# devBoard.net
KiCad netlist of a schematic drawn in Altium Designer
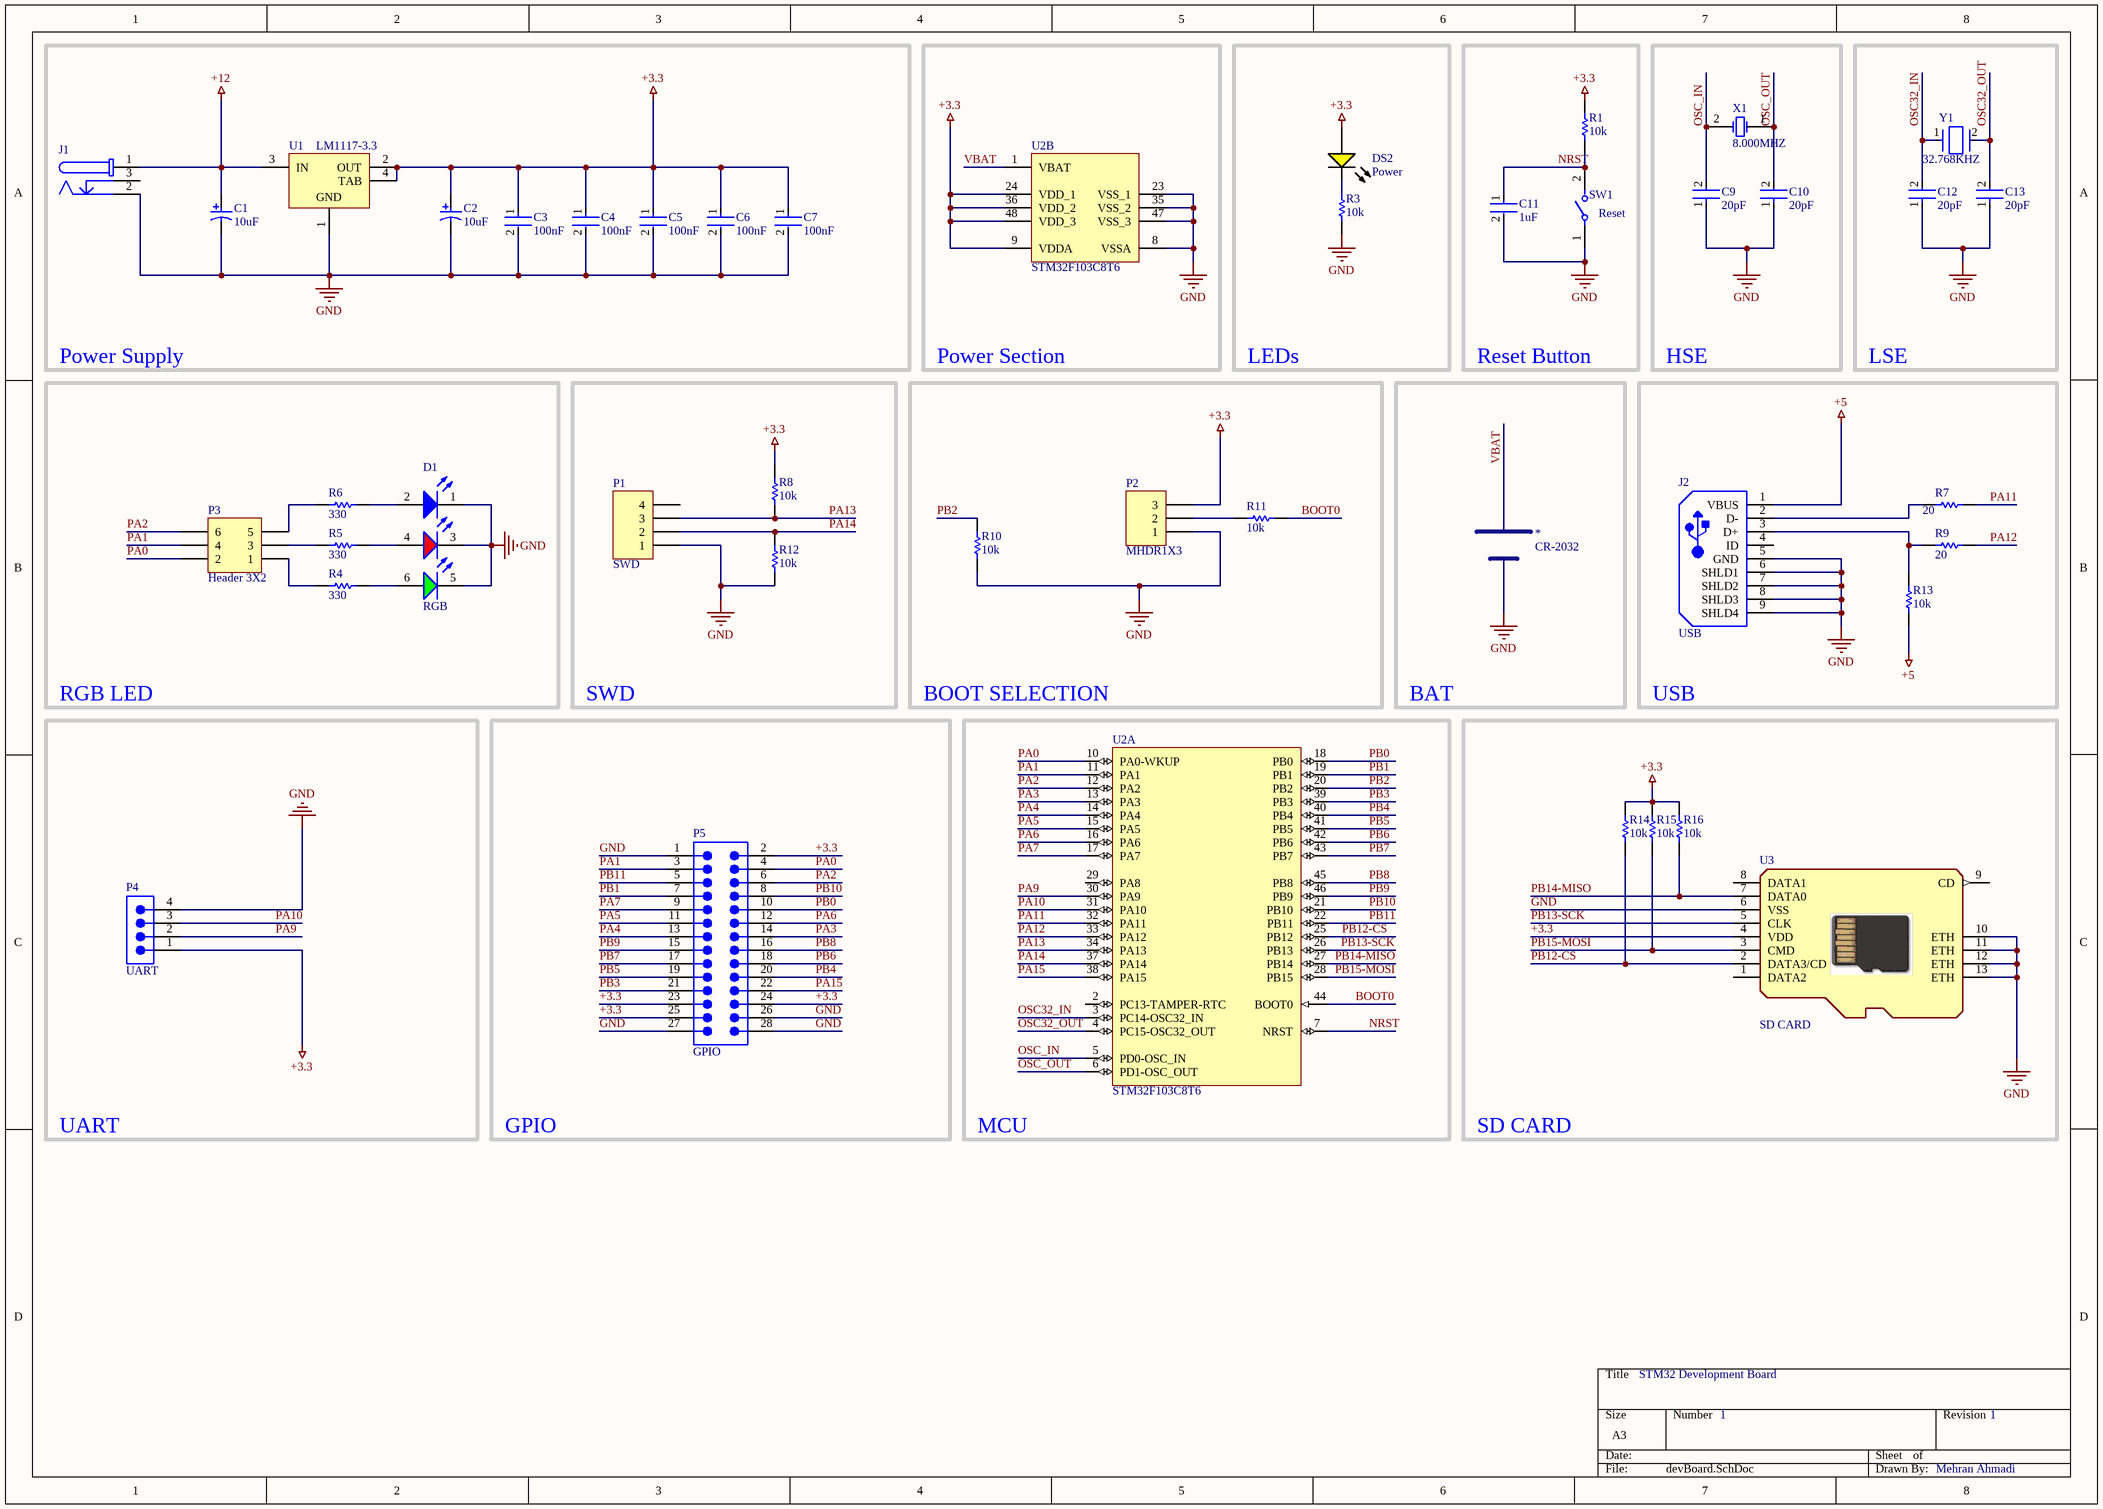
[diagram p0: devBoard.SchDoc]

(export (version "E")
  (design (tool "Eeschema 10.0.6"))
  (components
    (comp (ref "*")
      (value "CR-2032")
      (footprint "CR-2032")
      (libsource (lib "CR2032 Library") (part "CR-2032"))
    )
    (comp (ref "C1")
      (value "10uF")
      (footprint "PNSC-EEE1CA100SR_L")
      (description "Aluminum Electrolytic Capacitor, 10 uF, +/- 20%, -40 to 85 degC, 2-Pin SMD, RoHS, Tape and Reel")
      (fields (field (name "MANUFACTURER") "Panasonic"))
      (libsource (lib "Altium Content Vault") (part "CAP-P-2"))
    )
    (comp (ref "C2")
      (value "10uF")
      (footprint "PNSC-EEE1CA100SR_L")
      (description "Aluminum Electrolytic Capacitor, 10 uF, +/- 20%, -40 to 85 degC, 2-Pin SMD, RoHS, Tape and Reel")
      (fields (field (name "MANUFACTURER") "Panasonic"))
      (libsource (lib "Altium Content Vault") (part "CAP-P-2"))
    )
    (comp (ref "C3")
      (value "100nF")
      (footprint "FP-1206-L_3_2_0_2-W_1_6_0-MFG")
      (description "General Purpose Ceramic Capacitor, 1206, 100nF, 10%, X7R, 15%, 50V")
      (fields (field (name "TOLERANCE") "10%") (field (name "VOLTAGE") "50V"))
      (libsource (lib "Altium Content Vault") (part "02cd4be3c70576c341d710602a673aa"))
    )
    (comp (ref "C4")
      (value "100nF")
      (footprint "FP-1206-L_3_2_0_2-W_1_6_0-MFG")
      (description "General Purpose Ceramic Capacitor, 1206, 100nF, 10%, X7R, 15%, 50V")
      (fields (field (name "TOLERANCE") "10%") (field (name "VOLTAGE") "50V"))
      (libsource (lib "Altium Content Vault") (part "02cd4be3c70576c341d710602a673aa"))
    )
    (comp (ref "C5")
      (value "100nF")
      (footprint "FP-1206-L_3_2_0_2-W_1_6_0-MFG")
      (description "General Purpose Ceramic Capacitor, 1206, 100nF, 10%, X7R, 15%, 50V")
      (fields (field (name "TOLERANCE") "10%") (field (name "VOLTAGE") "50V"))
      (libsource (lib "Altium Content Vault") (part "02cd4be3c70576c341d710602a673aa"))
    )
    (comp (ref "C6")
      (value "100nF")
      (footprint "FP-1206-L_3_2_0_2-W_1_6_0-MFG")
      (description "General Purpose Ceramic Capacitor, 1206, 100nF, 10%, X7R, 15%, 50V")
      (fields (field (name "TOLERANCE") "10%") (field (name "VOLTAGE") "50V"))
      (libsource (lib "Altium Content Vault") (part "02cd4be3c70576c341d710602a673aa"))
    )
    (comp (ref "C7")
      (value "100nF")
      (footprint "FP-1206-L_3_2_0_2-W_1_6_0-MFG")
      (description "General Purpose Ceramic Capacitor, 1206, 100nF, 10%, X7R, 15%, 50V")
      (fields (field (name "TOLERANCE") "10%") (field (name "VOLTAGE") "50V"))
      (libsource (lib "Altium Content Vault") (part "02cd4be3c70576c341d710602a673aa"))
    )
    (comp (ref "C9")
      (value "20pF")
      (footprint "FP-CL31-IPC_A")
      (description "Cap Ceramic 20pF 50V C0G ±5% SMD 1206 +125°C Embossed T/R")
      (fields (field (name "TOLERANCE") "5%"))
      (libsource (lib "Altium Content Vault") (part "b4654b650e69147ec39a6b967a45e02"))
    )
    (comp (ref "C10")
      (value "20pF")
      (footprint "FP-CL31-IPC_A")
      (description "Cap Ceramic 20pF 50V C0G ±5% SMD 1206 +125°C Embossed T/R")
      (fields (field (name "TOLERANCE") "5%"))
      (libsource (lib "Altium Content Vault") (part "b4654b650e69147ec39a6b967a45e02"))
    )
    (comp (ref "C11")
      (value "1uF")
      (footprint "FP-1206-L_3_2_0_2-W_1_6_0-MFG")
      (description "General Purpose Ceramic Capacitor, 1206, 100nF, 10%, X7R, 15%, 50V")
      (fields (field (name "TOLERANCE") "10%") (field (name "VOLTAGE") "50V"))
      (libsource (lib "Altium Content Vault") (part "02cd4be3c70576c341d710602a673aa"))
    )
    (comp (ref "C12")
      (value "20pF")
      (footprint "FP-CL31-IPC_A")
      (description "Cap Ceramic 20pF 50V C0G ±5% SMD 1206 +125°C Embossed T/R")
      (fields (field (name "TOLERANCE") "5%"))
      (libsource (lib "Altium Content Vault") (part "b4654b650e69147ec39a6b967a45e02"))
    )
    (comp (ref "C13")
      (value "20pF")
      (footprint "FP-CL31-IPC_A")
      (description "Cap Ceramic 20pF 50V C0G ±5% SMD 1206 +125°C Embossed T/R")
      (fields (field (name "TOLERANCE") "5%"))
      (libsource (lib "Altium Content Vault") (part "b4654b650e69147ec39a6b967a45e02"))
    )
    (comp (ref "D1")
      (value "RGB")
      (footprint "WL-SFTW_5050_150505M173300")
      (description "150505M173300 WL-SFTW SMT full-color TOP LED waterclear")
      (libsource (lib "Altium Content Vault") (part "WL-SFTW_150505M173300"))
    )
    (comp (ref "DS2")
      (value "Power")
      (footprint "LUMX-SML-LX1206YC-TR_V")
      (description "Yellow LED, Water Clear Len, 585 nm, 2.1 V, -40 to 85 degC, 2-Pin SMD, RoHS, Tape and Reel")
      (fields (field (name "MANUFACTURER") "Lumex"))
      (libsource (lib "Altium Content Vault") (part "LED-YELLOW-AK-2"))
    )
    (comp (ref "J1")
      (value "~")
      (footprint "694106301002")
      (libsource (lib "Altium Content Vault") (part "DC Power Jack"))
    )
    (comp (ref "J2")
      (value "USB")
      (footprint "MOLX-56579-0576_V")
      (description "USB Connector, 30 V, 1 A, 0 to 50 degC, 5-Pin SMD, RoHS, Tape and Reel")
      (fields (field (name "MANUFACTURER") "Molex"))
      (libsource (lib "Altium Content Vault") (part "USB-5-4SHLD"))
    )
    (comp (ref "P1")
      (value "SWD")
      (footprint "HDR1X4")
      (description "Header, 4-Pin")
      (fields (field (name "PUBLISHER") "Altium Limited"))
      (libsource (lib "Miscellaneous Connectors") (part "Header 4"))
    )
    (comp (ref "P2")
      (value "MHDR1X3")
      (footprint "MHDR1X3")
      (description "Header, 3-Pin")
      (fields (field (name "PUBLISHER") "Altium Limited"))
      (libsource (lib "Miscellaneous Connectors") (part "MHDR1X3"))
    )
    (comp (ref "P3")
      (value "Header 3X2")
      (footprint "HDR2X3")
      (description "Header, 3-Pin, Dual row")
      (fields (field (name "PUBLISHER") "Altium Limited"))
      (libsource (lib "Miscellaneous Connectors") (part "Header 3X2"))
    )
    (comp (ref "P4")
      (value "UART")
      (footprint "61300411121")
      (libsource (lib "Altium Content Vault") (part "Header_Male_1R_04P"))
    )
    (comp (ref "P5")
      (value "GPIO")
      (footprint "61302821121")
      (libsource (lib "Altium Content Vault") (part "Header_Male_2R_28P"))
    )
    (comp (ref "R1")
      (value "10k")
      (footprint "RESC3116X65X40ML10T20")
      (description "Chip Resistor, 10 KOhm, +/- 1%, 0.25 W, -55 to 155 degC, 1206 (3216 Metric), RoHS, Tape and Reel")
      (fields (field (name "TOLERANCE") "1%") (field (name "MANUFACTURER") "Yageo"))
      (libsource (lib "Altium Content Vault") (part "RES-2"))
    )
    (comp (ref "R3")
      (value "10k")
      (footprint "RESC3116X65X40ML10T20")
      (description "Chip Resistor, 10 KOhm, +/- 1%, 0.25 W, -55 to 155 degC, 1206 (3216 Metric), RoHS, Tape and Reel")
      (fields (field (name "TOLERANCE") "1%") (field (name "MANUFACTURER") "Yageo"))
      (libsource (lib "Altium Content Vault") (part "RES-2"))
    )
    (comp (ref "R4")
      (value "330")
      (footprint "RESC3116X65X40ML10T20")
      (description "Chip Resistor, 10 KOhm, +/- 1%, 0.25 W, -55 to 155 degC, 1206 (3216 Metric), RoHS, Tape and Reel")
      (fields (field (name "TOLERANCE") "1%") (field (name "MANUFACTURER") "Yageo"))
      (libsource (lib "Altium Content Vault") (part "RES-2"))
    )
    (comp (ref "R5")
      (value "330")
      (footprint "RESC3116X65X40ML10T20")
      (description "Chip Resistor, 10 KOhm, +/- 1%, 0.25 W, -55 to 155 degC, 1206 (3216 Metric), RoHS, Tape and Reel")
      (fields (field (name "TOLERANCE") "1%") (field (name "MANUFACTURER") "Yageo"))
      (libsource (lib "Altium Content Vault") (part "RES-2"))
    )
    (comp (ref "R6")
      (value "330")
      (footprint "RESC3116X65X40ML10T20")
      (description "Chip Resistor, 10 KOhm, +/- 1%, 0.25 W, -55 to 155 degC, 1206 (3216 Metric), RoHS, Tape and Reel")
      (fields (field (name "TOLERANCE") "1%") (field (name "MANUFACTURER") "Yageo"))
      (libsource (lib "Altium Content Vault") (part "RES-2"))
    )
    (comp (ref "R7")
      (value "20")
      (footprint "RESC3116X65X40ML10T20")
      (description "Chip Resistor, 10 KOhm, +/- 1%, 0.25 W, -55 to 155 degC, 1206 (3216 Metric), RoHS, Tape and Reel")
      (fields (field (name "TOLERANCE") "1%") (field (name "MANUFACTURER") "Yageo"))
      (libsource (lib "Altium Content Vault") (part "RES-2"))
    )
    (comp (ref "R8")
      (value "10k")
      (footprint "RESC3116X65X40ML10T20")
      (description "Chip Resistor, 10 KOhm, +/- 1%, 0.25 W, -55 to 155 degC, 1206 (3216 Metric), RoHS, Tape and Reel")
      (fields (field (name "TOLERANCE") "1%") (field (name "MANUFACTURER") "Yageo"))
      (libsource (lib "Altium Content Vault") (part "RES-2"))
    )
    (comp (ref "R9")
      (value "20")
      (footprint "RESC3116X65X40ML10T20")
      (description "Chip Resistor, 10 KOhm, +/- 1%, 0.25 W, -55 to 155 degC, 1206 (3216 Metric), RoHS, Tape and Reel")
      (fields (field (name "TOLERANCE") "1%") (field (name "MANUFACTURER") "Yageo"))
      (libsource (lib "Altium Content Vault") (part "RES-2"))
    )
    (comp (ref "R10")
      (value "10k")
      (footprint "RESC3116X65X40ML10T20")
      (description "Chip Resistor, 10 KOhm, +/- 1%, 0.25 W, -55 to 155 degC, 1206 (3216 Metric), RoHS, Tape and Reel")
      (fields (field (name "TOLERANCE") "1%") (field (name "MANUFACTURER") "Yageo"))
      (libsource (lib "Altium Content Vault") (part "RES-2"))
    )
    (comp (ref "R11")
      (value "10k")
      (footprint "RESC3116X65X40ML10T20")
      (description "Chip Resistor, 10 KOhm, +/- 1%, 0.25 W, -55 to 155 degC, 1206 (3216 Metric), RoHS, Tape and Reel")
      (fields (field (name "TOLERANCE") "1%") (field (name "MANUFACTURER") "Yageo"))
      (libsource (lib "Altium Content Vault") (part "RES-2"))
    )
    (comp (ref "R12")
      (value "10k")
      (footprint "RESC3116X65X40ML10T20")
      (description "Chip Resistor, 10 KOhm, +/- 1%, 0.25 W, -55 to 155 degC, 1206 (3216 Metric), RoHS, Tape and Reel")
      (fields (field (name "TOLERANCE") "1%") (field (name "MANUFACTURER") "Yageo"))
      (libsource (lib "Altium Content Vault") (part "RES-2"))
    )
    (comp (ref "R13")
      (value "10k")
      (footprint "RESC3116X65X40ML10T20")
      (description "Chip Resistor, 10 KOhm, +/- 1%, 0.25 W, -55 to 155 degC, 1206 (3216 Metric), RoHS, Tape and Reel")
      (fields (field (name "TOLERANCE") "1%") (field (name "MANUFACTURER") "Yageo"))
      (libsource (lib "Altium Content Vault") (part "RES-2"))
    )
    (comp (ref "R14")
      (value "10k")
      (footprint "RESC3116X65X40ML10T20")
      (description "Chip Resistor, 10 KOhm, +/- 1%, 0.25 W, -55 to 155 degC, 1206 (3216 Metric), RoHS, Tape and Reel")
      (fields (field (name "TOLERANCE") "1%") (field (name "MANUFACTURER") "Yageo"))
      (libsource (lib "Altium Content Vault") (part "RES-2"))
    )
    (comp (ref "R15")
      (value "10k")
      (footprint "RESC3116X65X40ML10T20")
      (description "Chip Resistor, 10 KOhm, +/- 1%, 0.25 W, -55 to 155 degC, 1206 (3216 Metric), RoHS, Tape and Reel")
      (fields (field (name "TOLERANCE") "1%") (field (name "MANUFACTURER") "Yageo"))
      (libsource (lib "Altium Content Vault") (part "RES-2"))
    )
    (comp (ref "R16")
      (value "10k")
      (footprint "RESC3116X65X40ML10T20")
      (description "Chip Resistor, 10 KOhm, +/- 1%, 0.25 W, -55 to 155 degC, 1206 (3216 Metric), RoHS, Tape and Reel")
      (fields (field (name "TOLERANCE") "1%") (field (name "MANUFACTURER") "Yageo"))
      (libsource (lib "Altium Content Vault") (part "RES-2"))
    )
    (comp (ref "SW1")
      (value "Reset")
      (footprint "FP-1825965-1-MFG")
      (description "SWITCH TACTILE SPST-NO 0.05A 24V")
      (libsource (lib "Altium Content Vault") (part "bb27bde45df87f1f469753f287ef5ae"))
    )
    (comp (ref "U1")
      (value "LM1117-3.3")
      (footprint "DCY0004A_N")
      (description "800mA Low-Dropout Linear Regulator, 4-pin SOT-223, Pb-Free")
      (fields
        (field (name "PARTNUMBER") "LM1117IMP-3.3/NOPB")
        (field (name "MANUFACTURER") "Texas Instruments")
      )
      (libsource (lib "Altium Content Vault") (part "PM-REG-LM1086-SOT4"))
    )
    (comp (ref "U2")
      (value "STM32F103C8T6")
      (footprint "STM-LQFP48_L")
      (libsource (lib "Altium Content Vault") (part "MC-ARM-STM32F103X8_B-SQ48"))
    )
    (comp (ref "U3")
      (value "SD CARD")
      (footprint "TFWF1-EBXX-1X0X")
      (description "T-Flash 8pin SMT")
      (fields
        (field (name "MANUFACTURER") "Wellco T&C Co., Ltd.")
        (field (name "MANUFACTURE PART #") "TFWF1-EBXX-1X0X")
      )
      (libsource (lib "SDcard") (part "TFWF1-EBXX-1X0X"))
    )
    (comp (ref "X1")
      (value "8.000MHZ")
      (footprint "ABRA-ABLS-14.7456MHZ-B2-T_V")
      (description "Low Profile Crystal, 8.0 MHz, +/- 30 ppm, -20 to 70 degC, 2-Pin SMD, RoHS, Tape and Reel")
      (fields (field (name "MANUFACTURER") "ABRACON") (field (name "TOLERANCE") "30PPM"))
      (libsource (lib "Altium Content Vault") (part "XTAL_1-2-2"))
    )
    (comp (ref "Y1")
      (value "32.768KHZ")
      (footprint "FP-AB26TRB-MFG")
      (description "CRYSTAL 32.7680KHZ 12.5PF TH")
      (fields (field (name "TOLERANCE") "20ppm"))
      (libsource (lib "Altium Content Vault") (part "c23a69dc6c9e2f18f2079038eb95dd1"))
    )
  )
  (nets
    (net (code "1") (name "+3.3") (class "Default")
      (node (ref "C2") (pin "1") (pinfunction "1_1") (pintype "passive"))
      (node (ref "C3") (pin "1") (pinfunction "1_1") (pintype "passive"))
      (node (ref "C4") (pin "1") (pinfunction "1_1") (pintype "passive"))
      (node (ref "C5") (pin "1") (pinfunction "1_1") (pintype "passive"))
      (node (ref "C6") (pin "1") (pinfunction "1_1") (pintype "passive"))
      (node (ref "C7") (pin "1") (pinfunction "1_1") (pintype "passive"))
      (node (ref "DS2") (pin "1") (pinfunction "A_1") (pintype "passive"))
      (node (ref "P2") (pin "3") (pinfunction "3_3") (pintype "passive"))
      (node (ref "P4") (pin "1") (pinfunction "1_1") (pintype "passive"))
      (node (ref "P5") (pin "2") (pinfunction "2_2") (pintype "passive"))
      (node (ref "P5") (pin "23") (pinfunction "23_23") (pintype "passive"))
      (node (ref "P5") (pin "24") (pinfunction "24_24") (pintype "passive"))
      (node (ref "P5") (pin "25") (pinfunction "25_25") (pintype "passive"))
      (node (ref "R1") (pin "2") (pinfunction "2_2") (pintype "passive"))
      (node (ref "R14") (pin "1") (pinfunction "1_1") (pintype "passive"))
      (node (ref "R15") (pin "1") (pinfunction "1_1") (pintype "passive"))
      (node (ref "R16") (pin "1") (pinfunction "1_1") (pintype "passive"))
      (node (ref "R8") (pin "2") (pinfunction "2_2") (pintype "passive"))
      (node (ref "U1") (pin "2") (pinfunction "OUT_2") (pintype "power_in"))
      (node (ref "U1") (pin "4") (pinfunction "TAB_4") (pintype "power_in"))
      (node (ref "U2") (pin "24") (pinfunction "VDD_1_24") (pintype "power_in"))
      (node (ref "U2") (pin "36") (pinfunction "VDD_2_36") (pintype "power_in"))
      (node (ref "U2") (pin "48") (pinfunction "VDD_3_48") (pintype "power_in"))
      (node (ref "U2") (pin "9") (pinfunction "VDDA_9") (pintype "power_in"))
      (node (ref "U3") (pin "4") (pinfunction "VDD_4") (pintype "passive"))
    )
    (net (code "2") (name "+5") (class "Default")
      (node (ref "J2") (pin "1") (pinfunction "VBUS_1") (pintype "power_in"))
      (node (ref "R13") (pin "2") (pinfunction "2_2") (pintype "passive"))
    )
    (net (code "3") (name "+12") (class "Default")
      (node (ref "C1") (pin "1") (pinfunction "1_1") (pintype "passive"))
      (node (ref "J1") (pin "1") (pinfunction "1_1") (pintype "passive"))
      (node (ref "U1") (pin "3") (pinfunction "IN_3") (pintype "power_in"))
    )
    (net (code "4") (name "/BOOT0") (class "Default")
      (node (ref "R11") (pin "1") (pinfunction "1_1") (pintype "passive"))
      (node (ref "U2") (pin "44") (pinfunction "BOOT0_44") (pintype "input"))
    )
    (net (code "5") (name "/NRST") (class "Default")
      (node (ref "C11") (pin "1") (pinfunction "1_1") (pintype "passive"))
      (node (ref "R1") (pin "1") (pinfunction "1_1") (pintype "passive"))
      (node (ref "SW1") (pin "2") (pinfunction "2_2") (pintype "passive"))
      (node (ref "U2") (pin "7") (pinfunction "NRST_7") (pintype "bidirectional"))
    )
    (net (code "6") (name "/OSC32_IN") (class "Default")
      (node (ref "C12") (pin "2") (pinfunction "2_2") (pintype "passive"))
      (node (ref "U2") (pin "3") (pinfunction "PC14-OSC32_IN_3") (pintype "bidirectional"))
      (node (ref "Y1") (pin "1") (pinfunction "1_1") (pintype "passive"))
    )
    (net (code "7") (name "/OSC32_OUT") (class "Default")
      (node (ref "C13") (pin "2") (pinfunction "2_2") (pintype "passive"))
      (node (ref "U2") (pin "4") (pinfunction "PC15-OSC32_OUT_4") (pintype "bidirectional"))
      (node (ref "Y1") (pin "2") (pinfunction "2_2") (pintype "passive"))
    )
    (net (code "8") (name "/OSC_IN") (class "Default")
      (node (ref "C9") (pin "2") (pinfunction "2_2") (pintype "passive"))
      (node (ref "U2") (pin "5") (pinfunction "PD0-OSC_IN_5") (pintype "bidirectional"))
      (node (ref "X1") (pin "2") (pinfunction "X2_2") (pintype "passive"))
    )
    (net (code "9") (name "/OSC_OUT") (class "Default")
      (node (ref "C10") (pin "2") (pinfunction "2_2") (pintype "passive"))
      (node (ref "U2") (pin "6") (pinfunction "PD1-OSC_OUT_6") (pintype "bidirectional"))
      (node (ref "X1") (pin "1") (pinfunction "X1_1") (pintype "passive"))
    )
    (net (code "10") (name "/PA0") (class "Default")
      (node (ref "P3") (pin "2") (pinfunction "2_2") (pintype "passive"))
      (node (ref "P5") (pin "4") (pinfunction "4_4") (pintype "passive"))
      (node (ref "U2") (pin "10") (pinfunction "PA0-WKUP_10") (pintype "bidirectional"))
    )
    (net (code "11") (name "/PA1") (class "Default")
      (node (ref "P3") (pin "4") (pinfunction "4_4") (pintype "passive"))
      (node (ref "P5") (pin "3") (pinfunction "3_3") (pintype "passive"))
      (node (ref "U2") (pin "11") (pinfunction "PA1_11") (pintype "bidirectional"))
    )
    (net (code "12") (name "/PA2") (class "Default")
      (node (ref "P3") (pin "6") (pinfunction "6_6") (pintype "passive"))
      (node (ref "P5") (pin "6") (pinfunction "6_6") (pintype "passive"))
      (node (ref "U2") (pin "12") (pinfunction "PA2_12") (pintype "bidirectional"))
    )
    (net (code "13") (name "/PA3") (class "Default")
      (node (ref "P5") (pin "14") (pinfunction "14_14") (pintype "passive"))
      (node (ref "U2") (pin "13") (pinfunction "PA3_13") (pintype "bidirectional"))
    )
    (net (code "14") (name "/PA4") (class "Default")
      (node (ref "P5") (pin "13") (pinfunction "13_13") (pintype "passive"))
      (node (ref "U2") (pin "14") (pinfunction "PA4_14") (pintype "bidirectional"))
    )
    (net (code "15") (name "/PA5") (class "Default")
      (node (ref "P5") (pin "11") (pinfunction "11_11") (pintype "passive"))
      (node (ref "U2") (pin "15") (pinfunction "PA5_15") (pintype "bidirectional"))
    )
    (net (code "16") (name "/PA6") (class "Default")
      (node (ref "P5") (pin "12") (pinfunction "12_12") (pintype "passive"))
      (node (ref "U2") (pin "16") (pinfunction "PA6_16") (pintype "bidirectional"))
    )
    (net (code "17") (name "/PA7") (class "Default")
      (node (ref "P5") (pin "9") (pinfunction "9_9") (pintype "passive"))
      (node (ref "U2") (pin "17") (pinfunction "PA7_17") (pintype "bidirectional"))
    )
    (net (code "18") (name "/PA9") (class "Default")
      (node (ref "P4") (pin "2") (pinfunction "2_2") (pintype "passive"))
      (node (ref "U2") (pin "30") (pinfunction "PA9_30") (pintype "bidirectional"))
    )
    (net (code "19") (name "/PA10") (class "Default")
      (node (ref "P4") (pin "3") (pinfunction "3_3") (pintype "passive"))
      (node (ref "U2") (pin "31") (pinfunction "PA10_31") (pintype "bidirectional"))
    )
    (net (code "20") (name "/PA11") (class "Default")
      (node (ref "R7") (pin "2") (pinfunction "2_2") (pintype "passive"))
      (node (ref "U2") (pin "32") (pinfunction "PA11_32") (pintype "bidirectional"))
    )
    (net (code "21") (name "/PA12") (class "Default")
      (node (ref "R9") (pin "2") (pinfunction "2_2") (pintype "passive"))
      (node (ref "U2") (pin "33") (pinfunction "PA12_33") (pintype "bidirectional"))
    )
    (net (code "22") (name "/PA13") (class "Default")
      (node (ref "P1") (pin "3") (pinfunction "3_3") (pintype "passive"))
      (node (ref "R8") (pin "1") (pinfunction "1_1") (pintype "passive"))
      (node (ref "U2") (pin "34") (pinfunction "PA13_34") (pintype "bidirectional"))
    )
    (net (code "23") (name "/PA14") (class "Default")
      (node (ref "P1") (pin "2") (pinfunction "2_2") (pintype "passive"))
      (node (ref "R12") (pin "2") (pinfunction "2_2") (pintype "passive"))
      (node (ref "U2") (pin "37") (pinfunction "PA14_37") (pintype "bidirectional"))
    )
    (net (code "24") (name "/PA15") (class "Default")
      (node (ref "P5") (pin "22") (pinfunction "22_22") (pintype "passive"))
      (node (ref "U2") (pin "38") (pinfunction "PA15_38") (pintype "bidirectional"))
    )
    (net (code "25") (name "/PB0") (class "Default")
      (node (ref "P5") (pin "10") (pinfunction "10_10") (pintype "passive"))
      (node (ref "U2") (pin "18") (pinfunction "PB0_18") (pintype "bidirectional"))
    )
    (net (code "26") (name "/PB1") (class "Default")
      (node (ref "P5") (pin "7") (pinfunction "7_7") (pintype "passive"))
      (node (ref "U2") (pin "19") (pinfunction "PB1_19") (pintype "bidirectional"))
    )
    (net (code "27") (name "/PB2") (class "Default")
      (node (ref "R10") (pin "1") (pinfunction "1_1") (pintype "passive"))
      (node (ref "U2") (pin "20") (pinfunction "PB2_20") (pintype "bidirectional"))
    )
    (net (code "28") (name "/PB3") (class "Default")
      (node (ref "P5") (pin "21") (pinfunction "21_21") (pintype "passive"))
      (node (ref "U2") (pin "39") (pinfunction "PB3_39") (pintype "bidirectional"))
    )
    (net (code "29") (name "/PB4") (class "Default")
      (node (ref "P5") (pin "20") (pinfunction "20_20") (pintype "passive"))
      (node (ref "U2") (pin "40") (pinfunction "PB4_40") (pintype "bidirectional"))
    )
    (net (code "30") (name "/PB5") (class "Default")
      (node (ref "P5") (pin "19") (pinfunction "19_19") (pintype "passive"))
      (node (ref "U2") (pin "41") (pinfunction "PB5_41") (pintype "bidirectional"))
    )
    (net (code "31") (name "/PB6") (class "Default")
      (node (ref "P5") (pin "18") (pinfunction "18_18") (pintype "passive"))
      (node (ref "U2") (pin "42") (pinfunction "PB6_42") (pintype "bidirectional"))
    )
    (net (code "32") (name "/PB7") (class "Default")
      (node (ref "P5") (pin "17") (pinfunction "17_17") (pintype "passive"))
      (node (ref "U2") (pin "43") (pinfunction "PB7_43") (pintype "bidirectional"))
    )
    (net (code "33") (name "/PB8") (class "Default")
      (node (ref "P5") (pin "16") (pinfunction "16_16") (pintype "passive"))
      (node (ref "U2") (pin "45") (pinfunction "PB8_45") (pintype "bidirectional"))
    )
    (net (code "34") (name "/PB9") (class "Default")
      (node (ref "P5") (pin "15") (pinfunction "15_15") (pintype "passive"))
      (node (ref "U2") (pin "46") (pinfunction "PB9_46") (pintype "bidirectional"))
    )
    (net (code "35") (name "/PB10") (class "Default")
      (node (ref "P5") (pin "8") (pinfunction "8_8") (pintype "passive"))
      (node (ref "U2") (pin "21") (pinfunction "PB10_21") (pintype "bidirectional"))
    )
    (net (code "36") (name "/PB11") (class "Default")
      (node (ref "P5") (pin "5") (pinfunction "5_5") (pintype "passive"))
      (node (ref "U2") (pin "22") (pinfunction "PB11_22") (pintype "bidirectional"))
    )
    (net (code "37") (name "/PB12-CS") (class "Default")
      (node (ref "R14") (pin "2") (pinfunction "2_2") (pintype "passive"))
      (node (ref "U2") (pin "25") (pinfunction "PB12_25") (pintype "bidirectional"))
      (node (ref "U3") (pin "2") (pinfunction "DATA3/CD_2") (pintype "passive"))
    )
    (net (code "38") (name "/PB13-SCK") (class "Default")
      (node (ref "U2") (pin "26") (pinfunction "PB13_26") (pintype "bidirectional"))
      (node (ref "U3") (pin "5") (pinfunction "CLK_5") (pintype "passive"))
    )
    (net (code "39") (name "/PB14-MISO") (class "Default")
      (node (ref "R16") (pin "2") (pinfunction "2_2") (pintype "passive"))
      (node (ref "U2") (pin "27") (pinfunction "PB14_27") (pintype "bidirectional"))
      (node (ref "U3") (pin "7") (pinfunction "DATA0_7") (pintype "passive"))
    )
    (net (code "40") (name "/PB15-MOSI") (class "Default")
      (node (ref "R15") (pin "2") (pinfunction "2_2") (pintype "passive"))
      (node (ref "U2") (pin "28") (pinfunction "PB15_28") (pintype "bidirectional"))
      (node (ref "U3") (pin "3") (pinfunction "CMD_3") (pintype "passive"))
    )
    (net (code "41") (name "/VBAT") (class "Default")
      (node (ref "*") (pin "1") (pinfunction "1_1") (pintype "power_in"))
      (node (ref "U2") (pin "1") (pinfunction "VBAT_1") (pintype "power_in"))
    )
    (net (code "42") (name "GND") (class "Default")
      (node (ref "*") (pin "2") (pinfunction "2_2") (pintype "power_in"))
      (node (ref "C1") (pin "2") (pinfunction "2_2") (pintype "passive"))
      (node (ref "C10") (pin "1") (pinfunction "1_1") (pintype "passive"))
      (node (ref "C11") (pin "2") (pinfunction "2_2") (pintype "passive"))
      (node (ref "C12") (pin "1") (pinfunction "1_1") (pintype "passive"))
      (node (ref "C13") (pin "1") (pinfunction "1_1") (pintype "passive"))
      (node (ref "C2") (pin "2") (pinfunction "2_2") (pintype "passive"))
      (node (ref "C3") (pin "2") (pinfunction "2_2") (pintype "passive"))
      (node (ref "C4") (pin "2") (pinfunction "2_2") (pintype "passive"))
      (node (ref "C5") (pin "2") (pinfunction "2_2") (pintype "passive"))
      (node (ref "C6") (pin "2") (pinfunction "2_2") (pintype "passive"))
      (node (ref "C7") (pin "2") (pinfunction "2_2") (pintype "passive"))
      (node (ref "C9") (pin "1") (pinfunction "1_1") (pintype "passive"))
      (node (ref "D1") (pin "1") (pinfunction "K_1") (pintype "passive"))
      (node (ref "D1") (pin "3") (pinfunction "K_3") (pintype "passive"))
      (node (ref "D1") (pin "5") (pinfunction "K_5") (pintype "passive"))
      (node (ref "J1") (pin "2") (pinfunction "2_2") (pintype "passive"))
      (node (ref "J2") (pin "5") (pinfunction "GND_5") (pintype "power_in"))
      (node (ref "J2") (pin "6") (pinfunction "SHLD1_6") (pintype "passive"))
      (node (ref "J2") (pin "7") (pinfunction "SHLD2_7") (pintype "passive"))
      (node (ref "J2") (pin "8") (pinfunction "SHLD3_8") (pintype "passive"))
      (node (ref "J2") (pin "9") (pinfunction "SHLD4_9") (pintype "passive"))
      (node (ref "P1") (pin "1") (pinfunction "1_1") (pintype "passive"))
      (node (ref "P2") (pin "1") (pinfunction "1_1") (pintype "passive"))
      (node (ref "P4") (pin "4") (pinfunction "4_4") (pintype "passive"))
      (node (ref "P5") (pin "1") (pinfunction "1_1") (pintype "passive"))
      (node (ref "P5") (pin "26") (pinfunction "26_26") (pintype "passive"))
      (node (ref "P5") (pin "27") (pinfunction "27_27") (pintype "passive"))
      (node (ref "P5") (pin "28") (pinfunction "28_28") (pintype "passive"))
      (node (ref "R10") (pin "2") (pinfunction "2_2") (pintype "passive"))
      (node (ref "R12") (pin "1") (pinfunction "1_1") (pintype "passive"))
      (node (ref "R3") (pin "1") (pinfunction "1_1") (pintype "passive"))
      (node (ref "SW1") (pin "1") (pinfunction "1_1") (pintype "passive"))
      (node (ref "U1") (pin "1") (pinfunction "GND_1") (pintype "power_in"))
      (node (ref "U2") (pin "23") (pinfunction "VSS_1_23") (pintype "power_in"))
      (node (ref "U2") (pin "35") (pinfunction "VSS_2_35") (pintype "power_in"))
      (node (ref "U2") (pin "47") (pinfunction "VSS_3_47") (pintype "power_in"))
      (node (ref "U2") (pin "8") (pinfunction "VSSA_8") (pintype "power_in"))
      (node (ref "U3") (pin "10") (pinfunction "ETH_10") (pintype "passive"))
      (node (ref "U3") (pin "11") (pinfunction "ETH_11") (pintype "passive"))
      (node (ref "U3") (pin "12") (pinfunction "ETH_12") (pintype "passive"))
      (node (ref "U3") (pin "13") (pinfunction "ETH_13") (pintype "passive"))
      (node (ref "U3") (pin "6") (pinfunction "VSS_6") (pintype "passive"))
    )
    (net (code "43") (name "Net-(D1-A-Pad2)") (class "Default")
      (node (ref "D1") (pin "2") (pinfunction "A_2") (pintype "passive"))
      (node (ref "R6") (pin "1") (pinfunction "1_1") (pintype "passive"))
    )
    (net (code "44") (name "Net-(D1-A-Pad4)") (class "Default")
      (node (ref "D1") (pin "4") (pinfunction "A_4") (pintype "passive"))
      (node (ref "R5") (pin "1") (pinfunction "1_1") (pintype "passive"))
    )
    (net (code "45") (name "Net-(D1-A-Pad6)") (class "Default")
      (node (ref "D1") (pin "6") (pinfunction "A_6") (pintype "passive"))
      (node (ref "R4") (pin "1") (pinfunction "1_1") (pintype "passive"))
    )
    (net (code "46") (name "Net-(DS2-K)") (class "Default")
      (node (ref "DS2") (pin "2") (pinfunction "K_2") (pintype "passive"))
      (node (ref "R3") (pin "2") (pinfunction "2_2") (pintype "passive"))
    )
    (net (code "47") (name "Net-(J2-D+)") (class "Default")
      (node (ref "J2") (pin "3") (pinfunction "D+_3") (pintype "passive"))
      (node (ref "R13") (pin "1") (pinfunction "1_1") (pintype "passive"))
      (node (ref "R9") (pin "1") (pinfunction "1_1") (pintype "passive"))
    )
    (net (code "48") (name "Net-(J2-D-)") (class "Default")
      (node (ref "J2") (pin "2") (pinfunction "D-_2") (pintype "passive"))
      (node (ref "R7") (pin "1") (pinfunction "1_1") (pintype "passive"))
    )
    (net (code "49") (name "Net-(P2-Pad2)") (class "Default")
      (node (ref "P2") (pin "2") (pinfunction "2_2") (pintype "passive"))
      (node (ref "R11") (pin "2") (pinfunction "2_2") (pintype "passive"))
    )
    (net (code "50") (name "Net-(P3-Pad1)") (class "Default")
      (node (ref "P3") (pin "1") (pinfunction "1_1") (pintype "passive"))
      (node (ref "R4") (pin "2") (pinfunction "2_2") (pintype "passive"))
    )
    (net (code "51") (name "Net-(P3-Pad3)") (class "Default")
      (node (ref "P3") (pin "3") (pinfunction "3_3") (pintype "passive"))
      (node (ref "R5") (pin "2") (pinfunction "2_2") (pintype "passive"))
    )
    (net (code "52") (name "Net-(P3-Pad5)") (class "Default")
      (node (ref "P3") (pin "5") (pinfunction "5_5") (pintype "passive"))
      (node (ref "R6") (pin "2") (pinfunction "2_2") (pintype "passive"))
    )
    (net (code "53") (name "unconnected-(J1-Pad3)") (class "Default")
      (node (ref "J1") (pin "3") (pinfunction "3_3") (pintype "passive"))
    )
    (net (code "54") (name "unconnected-(J2-ID-Pad4)") (class "Default")
      (node (ref "J2") (pin "4") (pinfunction "ID_4") (pintype "passive"))
    )
    (net (code "55") (name "unconnected-(P1-Pad4)") (class "Default")
      (node (ref "P1") (pin "4") (pinfunction "4_4") (pintype "passive"))
    )
    (net (code "56") (name "unconnected-(U2A-PA8-Pad29)") (class "Default")
      (node (ref "U2") (pin "29") (pinfunction "PA8_29") (pintype "bidirectional"))
    )
    (net (code "57") (name "unconnected-(U2A-PC13-TAMPER-RTC-Pad2)") (class "Default")
      (node (ref "U2") (pin "2") (pinfunction "PC13-TAMPER-RTC_2") (pintype "bidirectional"))
    )
    (net (code "58") (name "unconnected-(U3-CD-Pad9)") (class "Default")
      (node (ref "U3") (pin "9") (pinfunction "CD_9") (pintype "output"))
    )
    (net (code "59") (name "unconnected-(U3-DATA1-Pad8)") (class "Default")
      (node (ref "U3") (pin "8") (pinfunction "DATA1_8") (pintype "passive"))
    )
    (net (code "60") (name "unconnected-(U3-DATA2-Pad1)") (class "Default")
      (node (ref "U3") (pin "1") (pinfunction "DATA2_1") (pintype "passive"))
    )
  )
)
